# LCDTFT_FPC40P_RGB_CTP.net
KiCad netlist of a schematic drawn in Altium Designer
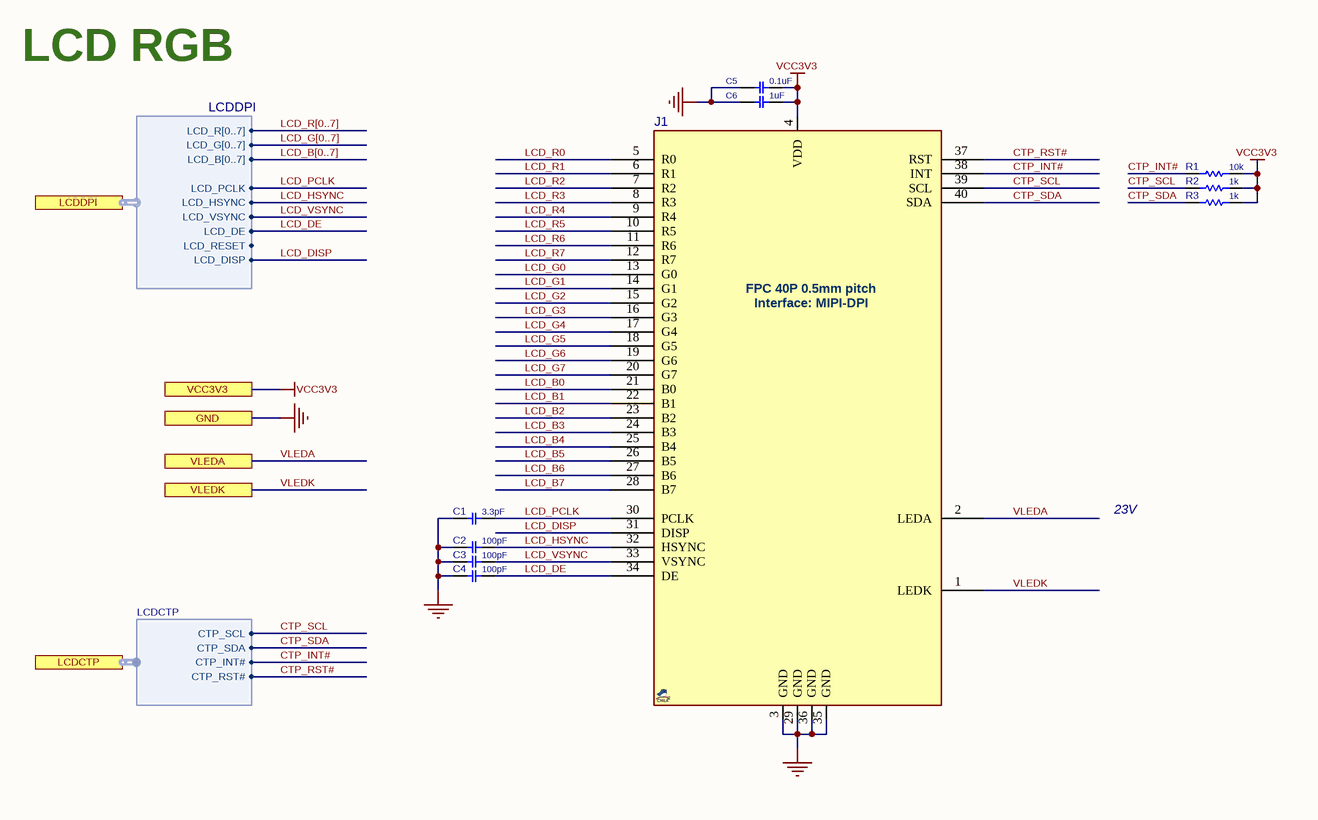
[diagram p0: LCDTFT_FPC40P_RGB_CTP.SchDoc]

(export (version "E")
  (design (tool "Eeschema 10.0.6"))
  (components
    (comp (ref "C1")
      (value "3.3pF")
      (footprint "C0402")
      (description "CAP, MLCC")
      (libsource (lib "passive_smd") (part "CAP_SMD_MLCC"))
    )
    (comp (ref "C2")
      (value "100pF")
      (footprint "C0402")
      (description "CAP, MLCC")
      (libsource (lib "passive_smd") (part "CAP_SMD_MLCC"))
    )
    (comp (ref "C3")
      (value "100pF")
      (footprint "C0402")
      (description "CAP, MLCC")
      (libsource (lib "passive_smd") (part "CAP_SMD_MLCC"))
    )
    (comp (ref "C4")
      (value "100pF")
      (footprint "C0402")
      (description "CAP, MLCC")
      (libsource (lib "passive_smd") (part "CAP_SMD_MLCC"))
    )
    (comp (ref "C5")
      (value "0.1uF")
      (footprint "C0402")
      (description "CAP, MLCC")
      (fields (field (name "MANF_P#") "GRM155R71H104KE14D") (field (name "MANF") "Murata"))
      (libsource (lib "passive_smd") (part "CAP_SMD_MLCC"))
    )
    (comp (ref "C6")
      (value "1uF")
      (footprint "C0402")
      (description "CAP, MLCC")
      (libsource (lib "passive_smd") (part "CAP_SMD_MLCC"))
    )
    (comp (ref "J1")
      (value "FPC_40_0.5mm")
      (footprint "FPC50_40")
      (description "LCD TFT Color, FPC40P, RGB")
      (libsource (lib "lcdtft") (part "LCDTFT_DPI_FPC40P_RK043FN48H"))
    )
    (comp (ref "R1")
      (value "10k")
      (footprint "R0402")
      (description "RESISTOR, SMD")
      (libsource (lib "passive_res_smd") (part "RES_SMD"))
    )
    (comp (ref "R2")
      (value "1k")
      (footprint "R0402")
      (description "RESISTOR, SMD")
      (libsource (lib "passive_res_smd") (part "RES_SMD"))
    )
    (comp (ref "R3")
      (value "1k")
      (footprint "R0402")
      (description "RESISTOR, SMD")
      (libsource (lib "passive_res_smd") (part "RES_SMD"))
    )
  )
  (nets
    (net (code "3") (name "/CTP_INT#") (class "Default")
      (node (ref "J1") (pin "38") (pinfunction "INT_38") (pintype "passive"))
      (node (ref "R1") (pin "1") (pinfunction "1_1") (pintype "passive"))
    )
    (net (code "4") (name "/CTP_RST#") (class "Default")
      (node (ref "J1") (pin "37") (pinfunction "RST_37") (pintype "passive"))
    )
    (net (code "5") (name "/CTP_SCL") (class "Default")
      (node (ref "J1") (pin "39") (pinfunction "SCL_39") (pintype "passive"))
      (node (ref "R2") (pin "1") (pinfunction "1_1") (pintype "passive"))
    )
    (net (code "6") (name "/CTP_SDA") (class "Default")
      (node (ref "J1") (pin "40") (pinfunction "SDA_40") (pintype "passive"))
      (node (ref "R3") (pin "1") (pinfunction "1_1") (pintype "passive"))
    )
    (net (code "7") (name "/LCD_B0") (class "Default")
      (node (ref "J1") (pin "21") (pinfunction "B0_21") (pintype "passive"))
    )
    (net (code "8") (name "/LCD_B1") (class "Default")
      (node (ref "J1") (pin "22") (pinfunction "B1_22") (pintype "passive"))
    )
    (net (code "9") (name "/LCD_B2") (class "Default")
      (node (ref "J1") (pin "23") (pinfunction "B2_23") (pintype "passive"))
    )
    (net (code "10") (name "/LCD_B3") (class "Default")
      (node (ref "J1") (pin "24") (pinfunction "B3_24") (pintype "passive"))
    )
    (net (code "11") (name "/LCD_B4") (class "Default")
      (node (ref "J1") (pin "25") (pinfunction "B4_25") (pintype "passive"))
    )
    (net (code "12") (name "/LCD_B5") (class "Default")
      (node (ref "J1") (pin "26") (pinfunction "B5_26") (pintype "passive"))
    )
    (net (code "13") (name "/LCD_B6") (class "Default")
      (node (ref "J1") (pin "27") (pinfunction "B6_27") (pintype "passive"))
    )
    (net (code "14") (name "/LCD_B7") (class "Default")
      (node (ref "J1") (pin "28") (pinfunction "B7_28") (pintype "passive"))
    )
    (net (code "16") (name "/LCD_DE") (class "Default")
      (node (ref "C4") (pin "1") (pinfunction "1_1") (pintype "passive"))
      (node (ref "J1") (pin "34") (pinfunction "DE_34") (pintype "passive"))
    )
    (net (code "17") (name "/LCD_DISP") (class "Default")
      (node (ref "J1") (pin "31") (pinfunction "DISP_31") (pintype "passive"))
    )
    (net (code "18") (name "/LCD_G0") (class "Default")
      (node (ref "J1") (pin "13") (pinfunction "G0_13") (pintype "passive"))
    )
    (net (code "19") (name "/LCD_G1") (class "Default")
      (node (ref "J1") (pin "14") (pinfunction "G1_14") (pintype "passive"))
    )
    (net (code "20") (name "/LCD_G2") (class "Default")
      (node (ref "J1") (pin "15") (pinfunction "G2_15") (pintype "passive"))
    )
    (net (code "21") (name "/LCD_G3") (class "Default")
      (node (ref "J1") (pin "16") (pinfunction "G3_16") (pintype "passive"))
    )
    (net (code "22") (name "/LCD_G4") (class "Default")
      (node (ref "J1") (pin "17") (pinfunction "G4_17") (pintype "passive"))
    )
    (net (code "23") (name "/LCD_G5") (class "Default")
      (node (ref "J1") (pin "18") (pinfunction "G5_18") (pintype "passive"))
    )
    (net (code "24") (name "/LCD_G6") (class "Default")
      (node (ref "J1") (pin "19") (pinfunction "G6_19") (pintype "passive"))
    )
    (net (code "25") (name "/LCD_G7") (class "Default")
      (node (ref "J1") (pin "20") (pinfunction "G7_20") (pintype "passive"))
    )
    (net (code "27") (name "/LCD_HSYNC") (class "Default")
      (node (ref "C2") (pin "1") (pinfunction "1_1") (pintype "passive"))
      (node (ref "J1") (pin "32") (pinfunction "HSYNC_32") (pintype "passive"))
    )
    (net (code "28") (name "/LCD_PCLK") (class "Default")
      (node (ref "C1") (pin "1") (pinfunction "1_1") (pintype "passive"))
      (node (ref "J1") (pin "30") (pinfunction "PCLK_30") (pintype "passive"))
    )
    (net (code "29") (name "/LCD_R0") (class "Default")
      (node (ref "J1") (pin "5") (pinfunction "R0_5") (pintype "passive"))
    )
    (net (code "30") (name "/LCD_R1") (class "Default")
      (node (ref "J1") (pin "6") (pinfunction "R1_6") (pintype "passive"))
    )
    (net (code "31") (name "/LCD_R2") (class "Default")
      (node (ref "J1") (pin "7") (pinfunction "R2_7") (pintype "passive"))
    )
    (net (code "32") (name "/LCD_R3") (class "Default")
      (node (ref "J1") (pin "8") (pinfunction "R3_8") (pintype "passive"))
    )
    (net (code "33") (name "/LCD_R4") (class "Default")
      (node (ref "J1") (pin "9") (pinfunction "R4_9") (pintype "passive"))
    )
    (net (code "34") (name "/LCD_R5") (class "Default")
      (node (ref "J1") (pin "10") (pinfunction "R5_10") (pintype "passive"))
    )
    (net (code "35") (name "/LCD_R6") (class "Default")
      (node (ref "J1") (pin "11") (pinfunction "R6_11") (pintype "passive"))
    )
    (net (code "36") (name "/LCD_R7") (class "Default")
      (node (ref "J1") (pin "12") (pinfunction "R7_12") (pintype "passive"))
    )
    (net (code "38") (name "/LCD_VSYNC") (class "Default")
      (node (ref "C3") (pin "1") (pinfunction "1_1") (pintype "passive"))
      (node (ref "J1") (pin "33") (pinfunction "VSYNC_33") (pintype "passive"))
    )
    (net (code "39") (name "/VLEDA") (class "Default")
      (node (ref "J1") (pin "2") (pinfunction "LEDA_2") (pintype "passive"))
    )
    (net (code "40") (name "/VLEDK") (class "Default")
      (node (ref "J1") (pin "1") (pinfunction "LEDK_1") (pintype "passive"))
    )
    (net (code "43") (name "GND") (class "Default")
      (node (ref "C1") (pin "2") (pinfunction "2_2") (pintype "passive"))
      (node (ref "C2") (pin "2") (pinfunction "2_2") (pintype "passive"))
      (node (ref "C3") (pin "2") (pinfunction "2_2") (pintype "passive"))
      (node (ref "C4") (pin "2") (pinfunction "2_2") (pintype "passive"))
      (node (ref "C5") (pin "2") (pinfunction "2_2") (pintype "passive"))
      (node (ref "C6") (pin "2") (pinfunction "2_2") (pintype "passive"))
      (node (ref "J1") (pin "29") (pinfunction "GND_29") (pintype "passive"))
      (node (ref "J1") (pin "3") (pinfunction "GND_3") (pintype "passive"))
      (node (ref "J1") (pin "35") (pinfunction "GND_35") (pintype "passive"))
      (node (ref "J1") (pin "36") (pinfunction "GND_36") (pintype "passive"))
    )
    (net (code "44") (name "VCC3V3") (class "Default")
      (node (ref "C5") (pin "1") (pinfunction "1_1") (pintype "passive"))
      (node (ref "C6") (pin "1") (pinfunction "1_1") (pintype "passive"))
      (node (ref "J1") (pin "4") (pinfunction "VDD_4") (pintype "passive"))
      (node (ref "R1") (pin "2") (pinfunction "2_2") (pintype "passive"))
      (node (ref "R2") (pin "2") (pinfunction "2_2") (pintype "passive"))
      (node (ref "R3") (pin "2") (pinfunction "2_2") (pintype "passive"))
    )
  )
)
